# flow_sensor.net
KiCad netlist of a schematic drawn in EAGLE
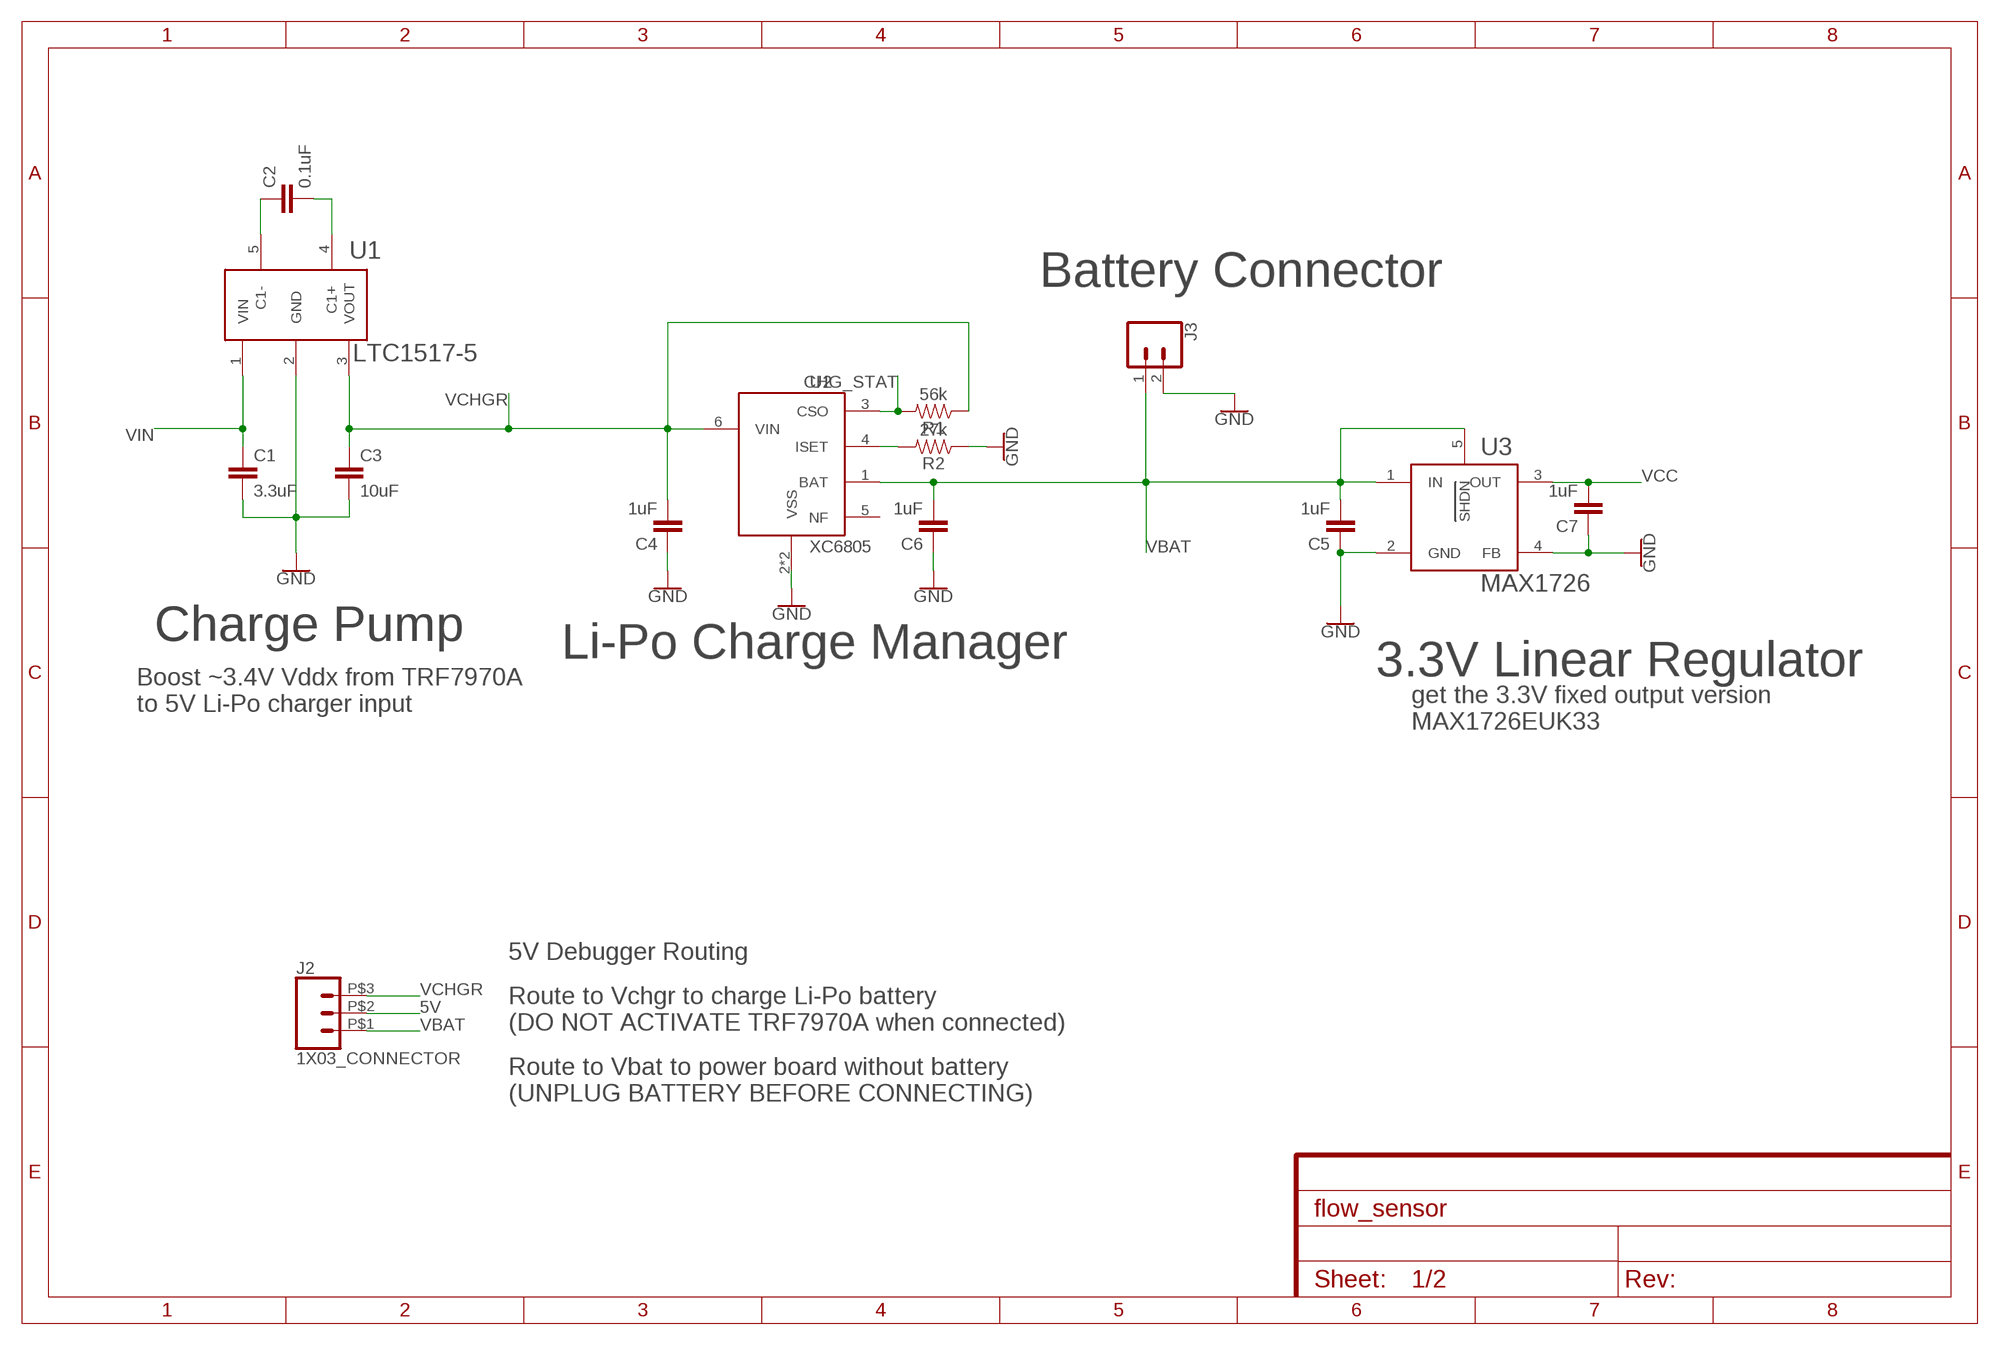
[diagram p0: schematic, sheet 1, part 1 of 2]
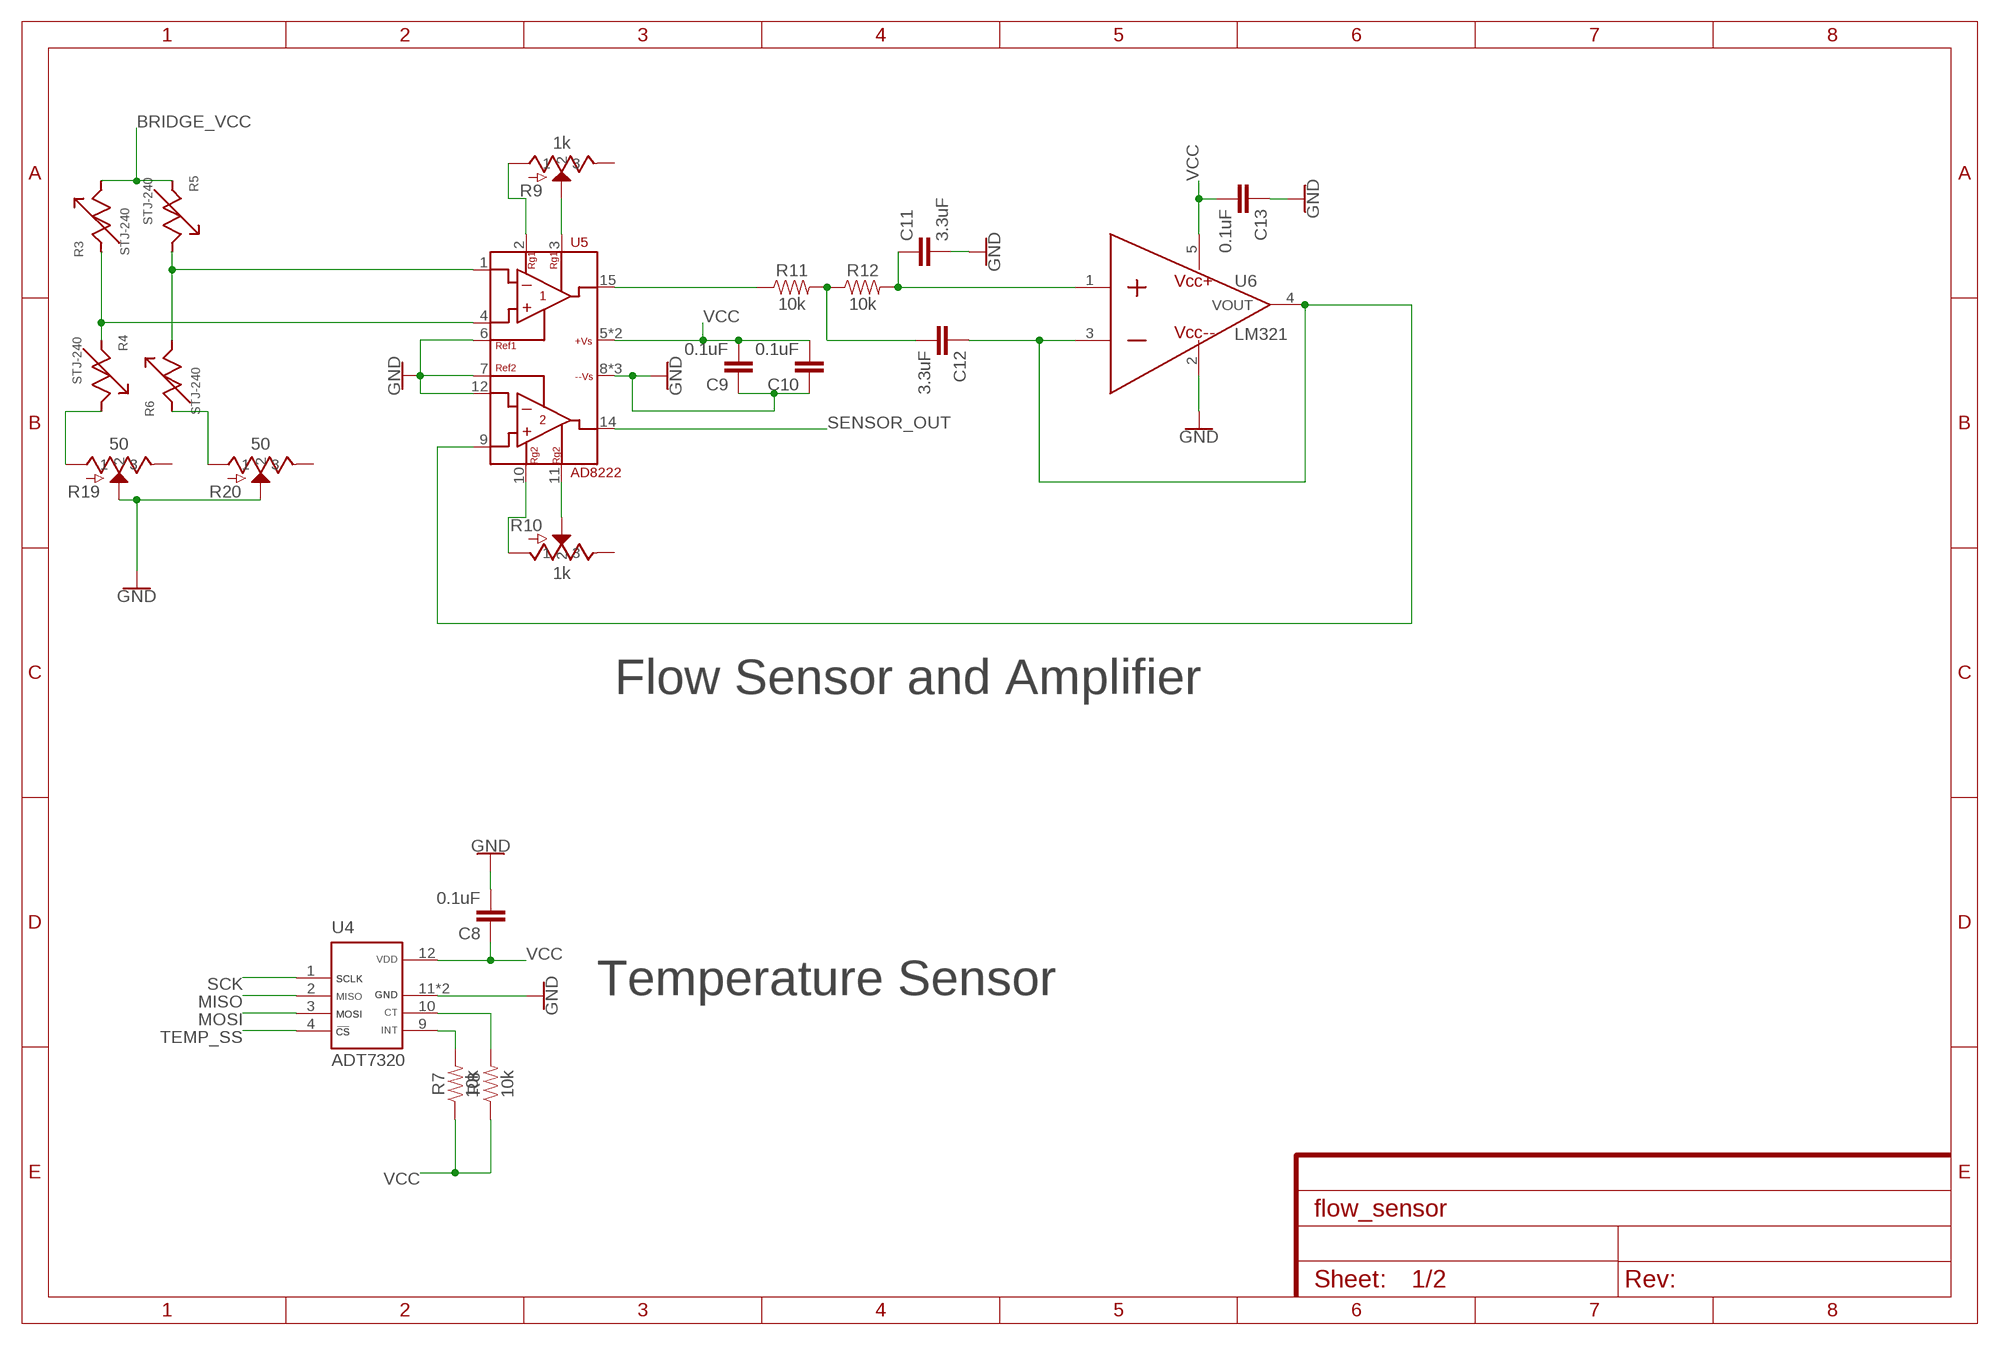
[diagram p1: schematic, sheet 1, part 2 of 2]
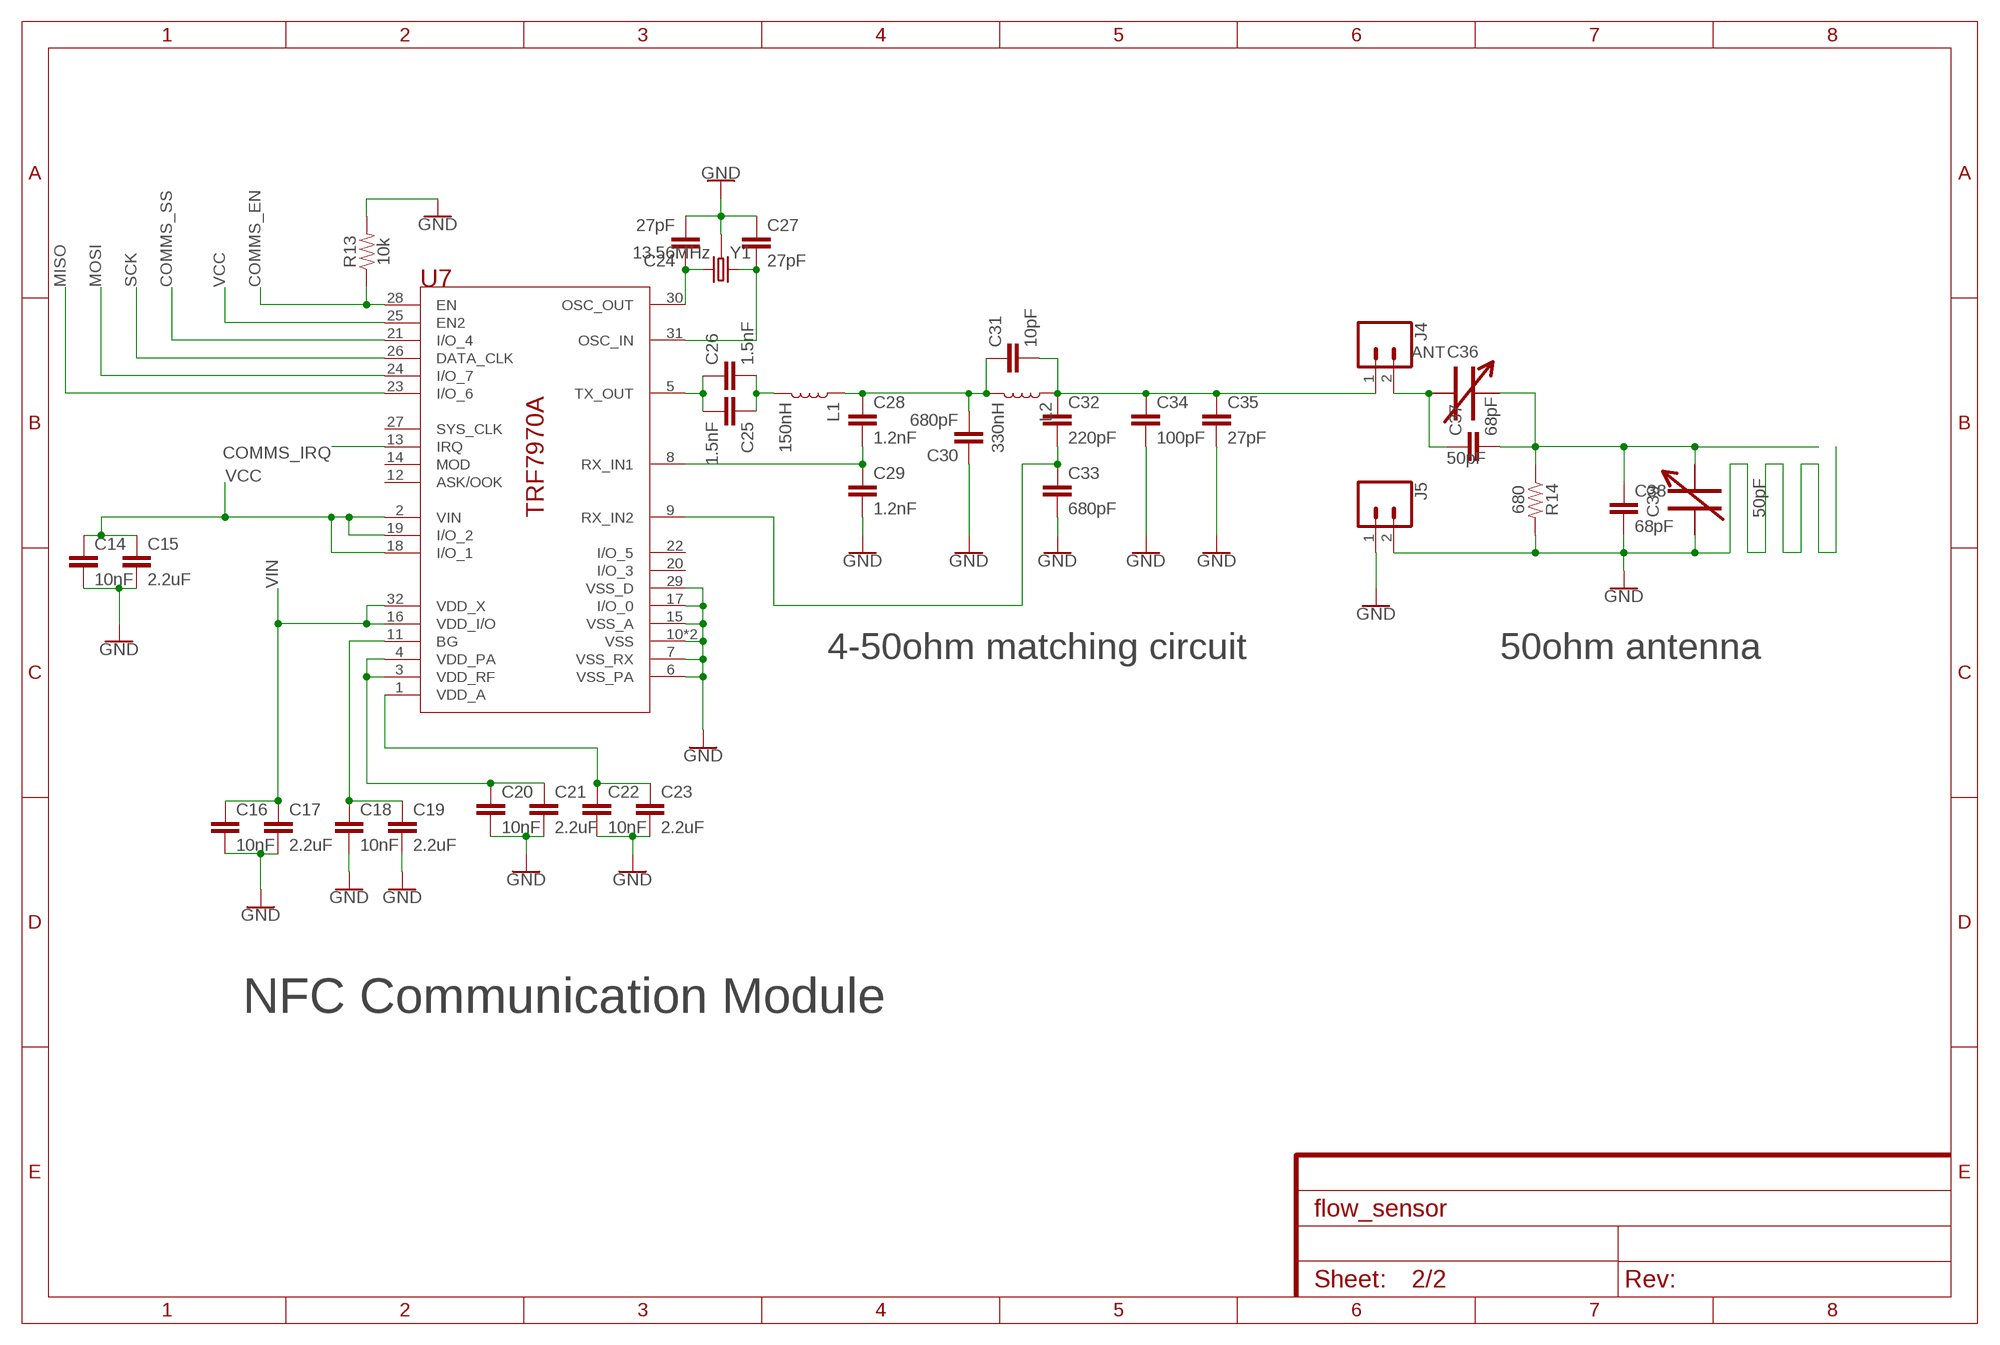
[diagram p2: schematic, sheet 2, part 1 of 2]
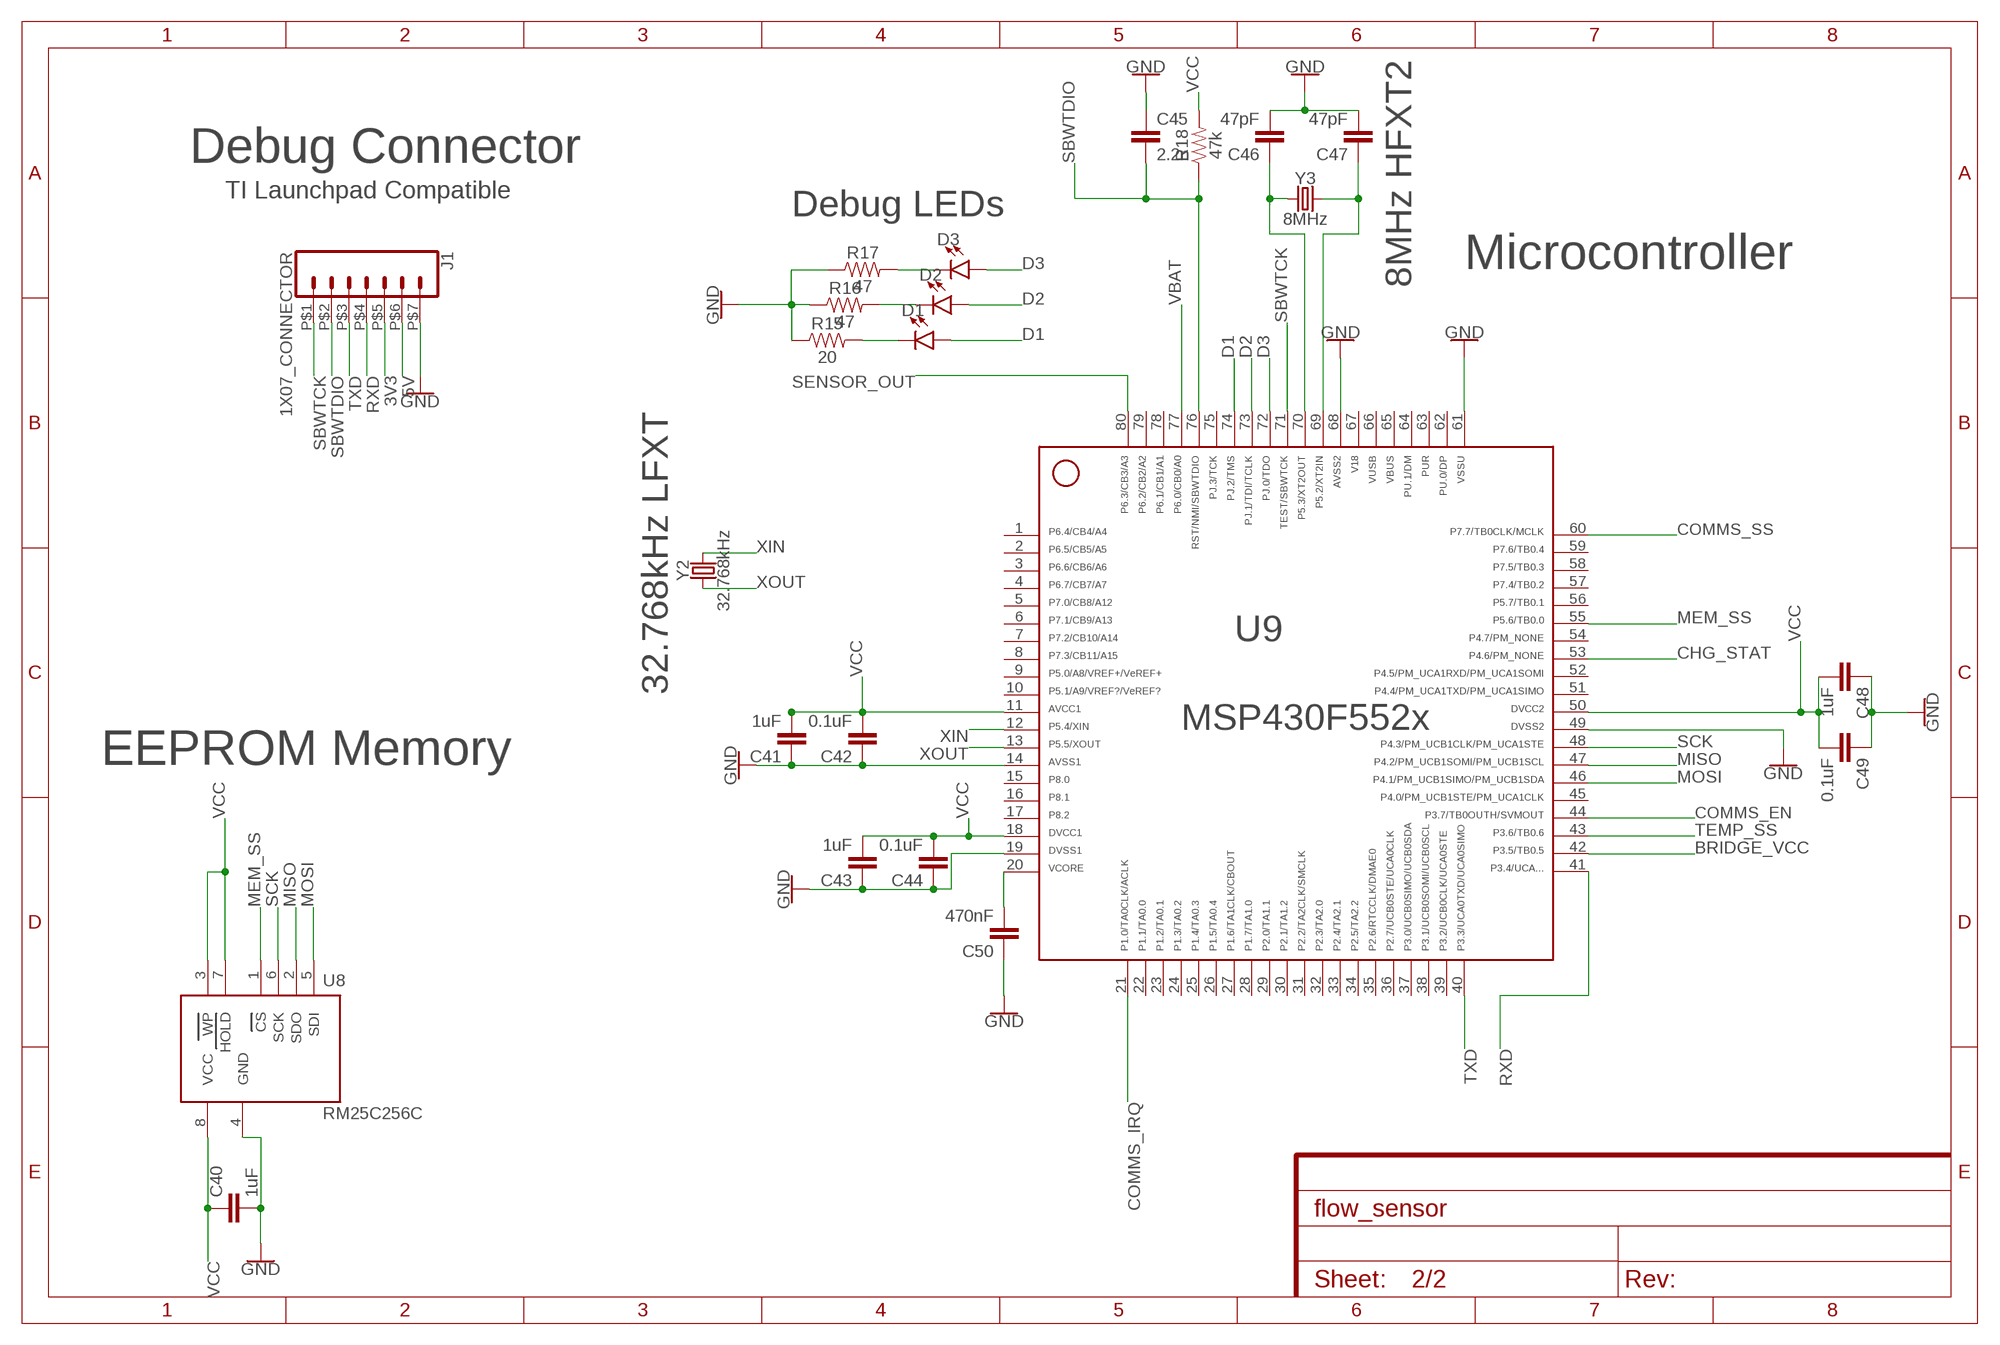
[diagram p3: schematic, sheet 2, part 2 of 2]

(export (version "E")
  (design (tool "Eeschema 10.0.6"))
  (components
    (comp (ref "C14")
      (value "10nF")
      (footprint "eagle-import:0603")
      (libsource (lib "eagle-import") (part "CAPACITOR_NONPOLARIZED"))
    )
    (comp (ref "C15")
      (value "2.2uF")
      (footprint "eagle-import:0603")
      (libsource (lib "eagle-import") (part "CAPACITOR_NONPOLARIZED"))
    )
    (comp (ref "C16")
      (value "10nF")
      (footprint "eagle-import:0603")
      (libsource (lib "eagle-import") (part "CAPACITOR_NONPOLARIZED"))
    )
    (comp (ref "C17")
      (value "2.2uF")
      (footprint "eagle-import:0603")
      (libsource (lib "eagle-import") (part "CAPACITOR_NONPOLARIZED"))
    )
    (comp (ref "C18")
      (value "10nF")
      (footprint "eagle-import:0603")
      (libsource (lib "eagle-import") (part "CAPACITOR_NONPOLARIZED"))
    )
    (comp (ref "C19")
      (value "2.2uF")
      (footprint "eagle-import:0603")
      (libsource (lib "eagle-import") (part "CAPACITOR_NONPOLARIZED"))
    )
    (comp (ref "C20")
      (value "10nF")
      (footprint "eagle-import:0603")
      (libsource (lib "eagle-import") (part "CAPACITOR_NONPOLARIZED"))
    )
    (comp (ref "C21")
      (value "2.2uF")
      (footprint "eagle-import:0603")
      (libsource (lib "eagle-import") (part "CAPACITOR_NONPOLARIZED"))
    )
    (comp (ref "C22")
      (value "10nF")
      (footprint "eagle-import:0603")
      (libsource (lib "eagle-import") (part "CAPACITOR_NONPOLARIZED"))
    )
    (comp (ref "C23")
      (value "2.2uF")
      (footprint "eagle-import:0603")
      (libsource (lib "eagle-import") (part "CAPACITOR_NONPOLARIZED"))
    )
    (comp (ref "C24")
      (value "27pF")
      (footprint "eagle-import:0603")
      (libsource (lib "eagle-import") (part "CAPACITOR_NONPOLARIZED"))
    )
    (comp (ref "C25")
      (value "1.5nF")
      (footprint "eagle-import:0603")
      (libsource (lib "eagle-import") (part "CAPACITOR_NONPOLARIZED"))
    )
    (comp (ref "C26")
      (value "1.5nF")
      (footprint "eagle-import:0603")
      (libsource (lib "eagle-import") (part "CAPACITOR_NONPOLARIZED"))
    )
    (comp (ref "C27")
      (value "27pF")
      (footprint "eagle-import:0603")
      (libsource (lib "eagle-import") (part "CAPACITOR_NONPOLARIZED"))
    )
    (comp (ref "C28")
      (value "1.2nF")
      (footprint "eagle-import:0603")
      (libsource (lib "eagle-import") (part "CAPACITOR_NONPOLARIZED"))
    )
    (comp (ref "C29")
      (value "1.2nF")
      (footprint "eagle-import:0603")
      (libsource (lib "eagle-import") (part "CAPACITOR_NONPOLARIZED"))
    )
    (comp (ref "C30")
      (value "680pF")
      (footprint "eagle-import:0603")
      (libsource (lib "eagle-import") (part "CAPACITOR_NONPOLARIZED"))
    )
    (comp (ref "C31")
      (value "10pF")
      (footprint "eagle-import:0603")
      (libsource (lib "eagle-import") (part "CAPACITOR_NONPOLARIZED"))
    )
    (comp (ref "C32")
      (value "220pF")
      (footprint "eagle-import:0603")
      (libsource (lib "eagle-import") (part "CAPACITOR_NONPOLARIZED"))
    )
    (comp (ref "C33")
      (value "680pF")
      (footprint "eagle-import:0603")
      (libsource (lib "eagle-import") (part "CAPACITOR_NONPOLARIZED"))
    )
    (comp (ref "C34")
      (value "100pF")
      (footprint "eagle-import:0603")
      (libsource (lib "eagle-import") (part "CAPACITOR_NONPOLARIZED"))
    )
    (comp (ref "C35")
      (value "27pF")
      (footprint "eagle-import:0603")
      (libsource (lib "eagle-import") (part "CAPACITOR_NONPOLARIZED"))
    )
    (comp (ref "C36")
      (value "50pF")
      (footprint "eagle-import:TZY2_TRIM_CAP")
      (libsource (lib "eagle-import") (part "TZY2_TRIM_CAP"))
    )
    (comp (ref "C37")
      (value "68pF")
      (footprint "eagle-import:C2.5-2")
      (libsource (lib "eagle-import") (part "C2.5/2"))
    )
    (comp (ref "C38")
      (value "68pF")
      (footprint "eagle-import:C2.5-2")
      (libsource (lib "eagle-import") (part "C2.5/2"))
    )
    (comp (ref "C39")
      (value "50pF")
      (footprint "eagle-import:TZY2_TRIM_CAP")
      (libsource (lib "eagle-import") (part "TZY2_TRIM_CAP"))
    )
    (comp (ref "C40")
      (value "1uF")
      (footprint "eagle-import:0603")
      (libsource (lib "eagle-import") (part "CAPACITOR_NONPOLARIZED"))
    )
    (comp (ref "C41")
      (value "1uF")
      (footprint "eagle-import:0603")
      (libsource (lib "eagle-import") (part "CAPACITOR_NONPOLARIZED"))
    )
    (comp (ref "C42")
      (value "0.1uF")
      (footprint "eagle-import:0603")
      (libsource (lib "eagle-import") (part "CAPACITOR_NONPOLARIZED"))
    )
    (comp (ref "C43")
      (value "1uF")
      (footprint "eagle-import:0603")
      (libsource (lib "eagle-import") (part "CAPACITOR_NONPOLARIZED"))
    )
    (comp (ref "C44")
      (value "0.1uF")
      (footprint "eagle-import:0603")
      (libsource (lib "eagle-import") (part "CAPACITOR_NONPOLARIZED"))
    )
    (comp (ref "C45")
      (value "2.2n")
      (footprint "eagle-import:0603")
      (libsource (lib "eagle-import") (part "CAPACITOR_NONPOLARIZED"))
    )
    (comp (ref "C46")
      (value "47pF")
      (footprint "eagle-import:0603")
      (libsource (lib "eagle-import") (part "CAPACITOR_NONPOLARIZED"))
    )
    (comp (ref "C47")
      (value "47pF")
      (footprint "eagle-import:0603")
      (libsource (lib "eagle-import") (part "CAPACITOR_NONPOLARIZED"))
    )
    (comp (ref "C48")
      (value "1uF")
      (footprint "eagle-import:0603")
      (libsource (lib "eagle-import") (part "CAPACITOR_NONPOLARIZED"))
    )
    (comp (ref "C49")
      (value "0.1uF")
      (footprint "eagle-import:0603")
      (libsource (lib "eagle-import") (part "CAPACITOR_NONPOLARIZED"))
    )
    (comp (ref "C50")
      (value "470nF")
      (footprint "eagle-import:0603")
      (libsource (lib "eagle-import") (part "CAPACITOR_NONPOLARIZED"))
    )
    (comp (ref "D1")
      (value "LED0603")
      (footprint "eagle-import:LED-0603")
      (libsource (lib "eagle-import") (part "LED0603"))
    )
    (comp (ref "D2")
      (value "LED0603")
      (footprint "eagle-import:LED-0603")
      (libsource (lib "eagle-import") (part "LED0603"))
    )
    (comp (ref "D3")
      (value "LED0603")
      (footprint "eagle-import:LED-0603")
      (libsource (lib "eagle-import") (part "LED0603"))
    )
    (comp (ref "J1")
      (value "1X07_CONNECTOR")
      (footprint "eagle-import:1X07_SMD_HEADER")
      (libsource (lib "eagle-import") (part "1X07_CONNECTOR"))
    )
    (comp (ref "J4")
      (value "CONN_02")
      (footprint "eagle-import:1X02")
      (libsource (lib "eagle-import") (part "CONN_02"))
    )
    (comp (ref "J5")
      (value "CONN_02")
      (footprint "eagle-import:1X02")
      (libsource (lib "eagle-import") (part "CONN_02"))
    )
    (comp (ref "L1")
      (value "150nH")
      (footprint "eagle-import:0603")
      (libsource (lib "eagle-import") (part "INDUCTOR"))
    )
    (comp (ref "L2")
      (value "330nH")
      (footprint "eagle-import:0603")
      (libsource (lib "eagle-import") (part "INDUCTOR"))
    )
    (comp (ref "R13")
      (value "10k")
      (footprint "eagle-import:0603")
      (libsource (lib "eagle-import") (part "RESISTOR"))
    )
    (comp (ref "R14")
      (value "680")
      (footprint "eagle-import:0603")
      (libsource (lib "eagle-import") (part "RESISTOR"))
    )
    (comp (ref "R15")
      (value "20")
      (footprint "eagle-import:0603")
      (libsource (lib "eagle-import") (part "RESISTOR"))
    )
    (comp (ref "R16")
      (value "47")
      (footprint "eagle-import:0603")
      (libsource (lib "eagle-import") (part "RESISTOR"))
    )
    (comp (ref "R17")
      (value "47")
      (footprint "eagle-import:0603")
      (libsource (lib "eagle-import") (part "RESISTOR"))
    )
    (comp (ref "R18")
      (value "47k")
      (footprint "eagle-import:0603")
      (libsource (lib "eagle-import") (part "RESISTOR"))
    )
    (comp (ref "U7")
      (value "TRF7970A")
      (footprint "eagle-import:QFN-32")
      (libsource (lib "eagle-import") (part "TRF7970A"))
    )
    (comp (ref "U8")
      (value "RM25C256C")
      (footprint "eagle-import:DFN8-2X3")
      (libsource (lib "eagle-import") (part "RM25C256C"))
    )
    (comp (ref "U9")
      (value "F552X---PN80")
      (footprint "eagle-import:PN80")
      (libsource (lib "eagle-import") (part "F552X---PN80"))
    )
    (comp (ref "Y1")
      (value "13.56MHz")
      (footprint "eagle-import:CRYSTAL-SMD-3.2X2.5MM")
      (libsource (lib "eagle-import") (part "CRYSTAL-GROUNDEDSMD-3.2X2.5"))
    )
    (comp (ref "Y2")
      (value "32.768kHz")
      (footprint "eagle-import:CRYSTAL-3.2X1.5")
      (libsource (lib "eagle-import") (part "CRYSTAL-3.2X1.5"))
    )
    (comp (ref "Y3")
      (value "8MHz")
      (footprint "eagle-import:CRYSTAL-3.2X2.5")
      (libsource (lib "eagle-import") (part "CRYSTAL-3.2X2.5"))
    )
    (comp (ref "C1")
      (value "3.3uF")
      (footprint "eagle-import:0603")
      (libsource (lib "eagle-import") (part "CAPACITOR_NONPOLARIZED"))
    )
    (comp (ref "C2")
      (value "0.1uF")
      (footprint "eagle-import:0603")
      (libsource (lib "eagle-import") (part "CAPACITOR_NONPOLARIZED"))
    )
    (comp (ref "C3")
      (value "10uF")
      (footprint "eagle-import:0603")
      (libsource (lib "eagle-import") (part "CAPACITOR_NONPOLARIZED"))
    )
    (comp (ref "C4")
      (value "1uF")
      (footprint "eagle-import:0603")
      (libsource (lib "eagle-import") (part "CAPACITOR_NONPOLARIZED"))
    )
    (comp (ref "C5")
      (value "1uF")
      (footprint "eagle-import:0603")
      (libsource (lib "eagle-import") (part "CAPACITOR_NONPOLARIZED"))
    )
    (comp (ref "C6")
      (value "1uF")
      (footprint "eagle-import:0603")
      (libsource (lib "eagle-import") (part "CAPACITOR_NONPOLARIZED"))
    )
    (comp (ref "C7")
      (value "1uF")
      (footprint "eagle-import:0603")
      (libsource (lib "eagle-import") (part "CAPACITOR_NONPOLARIZED"))
    )
    (comp (ref "C8")
      (value "0.1uF")
      (footprint "eagle-import:0603")
      (libsource (lib "eagle-import") (part "CAPACITOR_NONPOLARIZED"))
    )
    (comp (ref "C9")
      (value "0.1uF")
      (footprint "eagle-import:0603")
      (libsource (lib "eagle-import") (part "CAPACITOR_NONPOLARIZED"))
    )
    (comp (ref "C10")
      (value "0.1uF")
      (footprint "eagle-import:0603")
      (libsource (lib "eagle-import") (part "CAPACITOR_NONPOLARIZED"))
    )
    (comp (ref "C11")
      (value "3.3uF")
      (footprint "eagle-import:0603")
      (libsource (lib "eagle-import") (part "CAPACITOR_NONPOLARIZED"))
    )
    (comp (ref "C12")
      (value "3.3uF")
      (footprint "eagle-import:0603")
      (libsource (lib "eagle-import") (part "CAPACITOR_NONPOLARIZED"))
    )
    (comp (ref "C13")
      (value "0.1uF")
      (footprint "eagle-import:0603")
      (libsource (lib "eagle-import") (part "CAPACITOR_NONPOLARIZED"))
    )
    (comp (ref "J2")
      (value "1X03_CONNECTOR")
      (footprint "eagle-import:1X03_SMD_HEADER")
      (libsource (lib "eagle-import") (part "1X03_CONNECTOR"))
    )
    (comp (ref "J3")
      (value "CONN_021X02_NO_SILK")
      (footprint "eagle-import:1X02_NO_SILK")
      (libsource (lib "eagle-import") (part "CONN_021X02_NO_SILK"))
    )
    (comp (ref "R1")
      (value "56k")
      (footprint "eagle-import:0603")
      (libsource (lib "eagle-import") (part "RESISTOR"))
    )
    (comp (ref "R2")
      (value "27k")
      (footprint "eagle-import:0603")
      (libsource (lib "eagle-import") (part "RESISTOR"))
    )
    (comp (ref "R3")
      (value "STJ-240")
      (footprint "eagle-import:SOIC-8-NOCREAM")
      (libsource (lib "eagle-import") (part "STJ-240"))
    )
    (comp (ref "R4")
      (value "STJ-240")
      (footprint "eagle-import:SOIC-8-NOCREAM")
      (libsource (lib "eagle-import") (part "STJ-240"))
    )
    (comp (ref "R5")
      (value "STJ-240")
      (footprint "eagle-import:SOIC-8-NOCREAM")
      (libsource (lib "eagle-import") (part "STJ-240"))
    )
    (comp (ref "R6")
      (value "STJ-240")
      (footprint "eagle-import:SOIC-8-NOCREAM")
      (libsource (lib "eagle-import") (part "STJ-240"))
    )
    (comp (ref "R7")
      (value "10k")
      (footprint "eagle-import:0603")
      (libsource (lib "eagle-import") (part "RESISTOR"))
    )
    (comp (ref "R8")
      (value "10k")
      (footprint "eagle-import:0603")
      (libsource (lib "eagle-import") (part "RESISTOR"))
    )
    (comp (ref "R9")
      (value "1k")
      (footprint "eagle-import:ST-32ETA")
      (libsource (lib "eagle-import") (part "ST-32ETA"))
    )
    (comp (ref "R10")
      (value "1k")
      (footprint "eagle-import:ST-32ETA")
      (libsource (lib "eagle-import") (part "ST-32ETA"))
    )
    (comp (ref "R11")
      (value "10k")
      (footprint "eagle-import:0603")
      (libsource (lib "eagle-import") (part "RESISTOR"))
    )
    (comp (ref "R12")
      (value "10k")
      (footprint "eagle-import:0603")
      (libsource (lib "eagle-import") (part "RESISTOR"))
    )
    (comp (ref "R19")
      (value "50")
      (footprint "eagle-import:ST-32ETA")
      (libsource (lib "eagle-import") (part "ST-32ETA"))
    )
    (comp (ref "R20")
      (value "50")
      (footprint "eagle-import:ST-32ETA")
      (libsource (lib "eagle-import") (part "ST-32ETA"))
    )
    (comp (ref "U1")
      (value "LTC1517-5")
      (footprint "eagle-import:SOT-23-5")
      (libsource (lib "eagle-import") (part "LTC1517-5"))
    )
    (comp (ref "U2")
      (value "XC6805")
      (footprint "eagle-import:DFN6-1.8X2.0")
      (libsource (lib "eagle-import") (part "XC6805"))
    )
    (comp (ref "U3")
      (value "MAX1726")
      (footprint "eagle-import:SOT-23-5")
      (libsource (lib "eagle-import") (part "MAX1726"))
    )
    (comp (ref "U4")
      (value "ADT7320")
      (footprint "eagle-import:QFN16-4X4")
      (libsource (lib "eagle-import") (part "ADT7320"))
    )
    (comp (ref "U5")
      (value "AD8222")
      (footprint "eagle-import:QFN16-4X4")
      (libsource (lib "eagle-import") (part "AD8222"))
    )
    (comp (ref "U6")
      (value "LM321")
      (footprint "eagle-import:SOT-23-5")
      (libsource (lib "eagle-import") (part "LM321"))
    )
  )
  (nets
    (net (code "1") (name "3V3") (class "Default")
      (node (ref "J1") (pin "P$5") (pinfunction "5_P$5") (pintype "passive"))
    )
    (net (code "2") (name "5V") (class "Default")
      (node (ref "J1") (pin "P$6") (pinfunction "6_P$6") (pintype "passive"))
      (node (ref "J2") (pin "P$2") (pinfunction "2_P$2") (pintype "passive"))
    )
    (net (code "3") (name "65") (class "Default")
      (node (ref "U9") (pin "65") (pinfunction "65_65") (pintype "power_in"))
    )
    (net (code "4") (name "66") (class "Default")
      (node (ref "U9") (pin "66") (pinfunction "66_66") (pintype "power_in"))
    )
    (net (code "5") (name "67") (class "Default")
      (node (ref "U9") (pin "67") (pinfunction "67_67") (pintype "power_in"))
    )
    (net (code "6") (name "ANT") (class "Default")
      (node (ref "C31") (pin "2") (pinfunction "2_2") (pintype "passive"))
      (node (ref "C32") (pin "1") (pinfunction "1_1") (pintype "passive"))
      (node (ref "C34") (pin "1") (pinfunction "1_1") (pintype "passive"))
      (node (ref "C35") (pin "1") (pinfunction "1_1") (pintype "passive"))
      (node (ref "J4") (pin "1") (pinfunction "1_1") (pintype "passive"))
      (node (ref "L2") (pin "1") (pinfunction "1_1") (pintype "passive"))
    )
    (net (code "7") (name "BRIDGE_VCC") (class "Default")
      (node (ref "R3") (pin "8") (pinfunction "P$2_8") (pintype "bidirectional"))
      (node (ref "R5") (pin "1") (pinfunction "P$1_1") (pintype "bidirectional"))
      (node (ref "U9") (pin "42") (pinfunction "42_42") (pintype "bidirectional"))
    )
    (net (code "8") (name "CHG_STAT") (class "Default")
      (node (ref "R1") (pin "2") (pinfunction "2_2") (pintype "passive"))
      (node (ref "U2") (pin "3") (pinfunction "CSO_3") (pintype "bidirectional"))
      (node (ref "U9") (pin "53") (pinfunction "53_53") (pintype "bidirectional"))
    )
    (net (code "9") (name "COMMS_EN") (class "Default")
      (node (ref "R13") (pin "1") (pinfunction "1_1") (pintype "passive"))
      (node (ref "U7") (pin "28") (pinfunction "EN_28") (pintype "bidirectional"))
      (node (ref "U9") (pin "44") (pinfunction "44_44") (pintype "bidirectional"))
    )
    (net (code "10") (name "COMMS_IRQ") (class "Default")
      (node (ref "U7") (pin "13") (pinfunction "IRQ_13") (pintype "bidirectional"))
      (node (ref "U9") (pin "21") (pinfunction "21_21") (pintype "bidirectional"))
    )
    (net (code "11") (name "COMMS_SS") (class "Default")
      (node (ref "U7") (pin "21") (pinfunction "I/O_4_21") (pintype "bidirectional"))
      (node (ref "U9") (pin "60") (pinfunction "60_60") (pintype "bidirectional"))
    )
    (net (code "12") (name "D1") (class "Default")
      (node (ref "D1") (pin "A") (pinfunction "A_A") (pintype "passive"))
      (node (ref "U9") (pin "74") (pinfunction "74_74") (pintype "bidirectional"))
    )
    (net (code "13") (name "D2") (class "Default")
      (node (ref "D2") (pin "A") (pinfunction "A_A") (pintype "passive"))
      (node (ref "U9") (pin "73") (pinfunction "73_73") (pintype "bidirectional"))
    )
    (net (code "14") (name "D3") (class "Default")
      (node (ref "D3") (pin "A") (pinfunction "A_A") (pintype "passive"))
      (node (ref "U9") (pin "72") (pinfunction "72_72") (pintype "bidirectional"))
    )
    (net (code "15") (name "GND") (class "Default")
      (node (ref "C1") (pin "2") (pinfunction "2_2") (pintype "passive"))
      (node (ref "C10") (pin "1") (pinfunction "1_1") (pintype "passive"))
      (node (ref "C11") (pin "2") (pinfunction "2_2") (pintype "passive"))
      (node (ref "C13") (pin "1") (pinfunction "1_1") (pintype "passive"))
      (node (ref "C14") (pin "2") (pinfunction "2_2") (pintype "passive"))
      (node (ref "C15") (pin "2") (pinfunction "2_2") (pintype "passive"))
      (node (ref "C16") (pin "2") (pinfunction "2_2") (pintype "passive"))
      (node (ref "C17") (pin "2") (pinfunction "2_2") (pintype "passive"))
      (node (ref "C18") (pin "2") (pinfunction "2_2") (pintype "passive"))
      (node (ref "C19") (pin "2") (pinfunction "2_2") (pintype "passive"))
      (node (ref "C20") (pin "2") (pinfunction "2_2") (pintype "passive"))
      (node (ref "C21") (pin "2") (pinfunction "2_2") (pintype "passive"))
      (node (ref "C22") (pin "2") (pinfunction "2_2") (pintype "passive"))
      (node (ref "C23") (pin "2") (pinfunction "2_2") (pintype "passive"))
      (node (ref "C24") (pin "2") (pinfunction "2_2") (pintype "passive"))
      (node (ref "C27") (pin "1") (pinfunction "1_1") (pintype "passive"))
      (node (ref "C29") (pin "2") (pinfunction "2_2") (pintype "passive"))
      (node (ref "C3") (pin "2") (pinfunction "2_2") (pintype "passive"))
      (node (ref "C30") (pin "1") (pinfunction "1_1") (pintype "passive"))
      (node (ref "C33") (pin "2") (pinfunction "2_2") (pintype "passive"))
      (node (ref "C34") (pin "2") (pinfunction "2_2") (pintype "passive"))
      (node (ref "C35") (pin "2") (pinfunction "2_2") (pintype "passive"))
      (node (ref "C38") (pin "2") (pinfunction "2_2") (pintype "passive"))
      (node (ref "C39") (pin "P$1") (pinfunction "P$1_P$1") (pintype "bidirectional"))
      (node (ref "C4") (pin "1") (pinfunction "1_1") (pintype "passive"))
      (node (ref "C40") (pin "2") (pinfunction "2_2") (pintype "passive"))
      (node (ref "C41") (pin "1") (pinfunction "1_1") (pintype "passive"))
      (node (ref "C42") (pin "1") (pinfunction "1_1") (pintype "passive"))
      (node (ref "C43") (pin "1") (pinfunction "1_1") (pintype "passive"))
      (node (ref "C44") (pin "1") (pinfunction "1_1") (pintype "passive"))
      (node (ref "C45") (pin "1") (pinfunction "1_1") (pintype "passive"))
      (node (ref "C46") (pin "2") (pinfunction "2_2") (pintype "passive"))
      (node (ref "C47") (pin "2") (pinfunction "2_2") (pintype "passive"))
      (node (ref "C48") (pin "1") (pinfunction "1_1") (pintype "passive"))
      (node (ref "C49") (pin "1") (pinfunction "1_1") (pintype "passive"))
      (node (ref "C5") (pin "1") (pinfunction "1_1") (pintype "passive"))
      (node (ref "C50") (pin "1") (pinfunction "1_1") (pintype "passive"))
      (node (ref "C6") (pin "1") (pinfunction "1_1") (pintype "passive"))
      (node (ref "C7") (pin "1") (pinfunction "1_1") (pintype "passive"))
      (node (ref "C8") (pin "2") (pinfunction "2_2") (pintype "passive"))
      (node (ref "C9") (pin "1") (pinfunction "1_1") (pintype "passive"))
      (node (ref "J1") (pin "P$7") (pinfunction "7_P$7") (pintype "passive"))
      (node (ref "J3") (pin "2") (pinfunction "2_2") (pintype "passive"))
      (node (ref "J5") (pin "1") (pinfunction "1_1") (pintype "passive"))
      (node (ref "J5") (pin "2") (pinfunction "2_2") (pintype "passive"))
      (node (ref "R13") (pin "2") (pinfunction "2_2") (pintype "passive"))
      (node (ref "R14") (pin "2") (pinfunction "2_2") (pintype "passive"))
      (node (ref "R15") (pin "1") (pinfunction "1_1") (pintype "passive"))
      (node (ref "R16") (pin "1") (pinfunction "1_1") (pintype "passive"))
      (node (ref "R17") (pin "1") (pinfunction "1_1") (pintype "passive"))
      (node (ref "R19") (pin "2") (pinfunction "2_2") (pintype "passive"))
      (node (ref "R2") (pin "1") (pinfunction "1_1") (pintype "passive"))
      (node (ref "R20") (pin "2") (pinfunction "2_2") (pintype "passive"))
      (node (ref "U1") (pin "2") (pinfunction "GND_2") (pintype "bidirectional"))
      (node (ref "U2") (pin "2") (pinfunction "VSS_2") (pintype "bidirectional"))
      (node (ref "U2") (pin "PAD") (pinfunction "VSS_PAD") (pintype "bidirectional"))
      (node (ref "U3") (pin "2") (pinfunction "GND_2") (pintype "bidirectional"))
      (node (ref "U3") (pin "4") (pinfunction "FB_4") (pintype "bidirectional"))
      (node (ref "U4") (pin "11") (pinfunction "GND_11") (pintype "bidirectional"))
      (node (ref "U4") (pin "EXP") (pinfunction "GND_EXP") (pintype "bidirectional"))
      (node (ref "U5") (pin "12") (pinfunction "-IN2_12") (pintype "bidirectional"))
      (node (ref "U5") (pin "13") (pinfunction "-VS_13") (pintype "bidirectional"))
      (node (ref "U5") (pin "6") (pinfunction "REF1_6") (pintype "bidirectional"))
      (node (ref "U5") (pin "7") (pinfunction "REF2_7") (pintype "bidirectional"))
      (node (ref "U5") (pin "8") (pinfunction "-VS_8") (pintype "bidirectional"))
      (node (ref "U5") (pin "EXP") (pinfunction "-VS_EXP") (pintype "bidirectional"))
      (node (ref "U6") (pin "2") (pinfunction "VCC-_2") (pintype "power_in"))
      (node (ref "U7") (pin "10") (pinfunction "VSS_10") (pintype "bidirectional"))
      (node (ref "U7") (pin "15") (pinfunction "VSS_A_15") (pintype "bidirectional"))
      (node (ref "U7") (pin "17") (pinfunction "I/O_0_17") (pintype "bidirectional"))
      (node (ref "U7") (pin "29") (pinfunction "VSS_D_29") (pintype "bidirectional"))
      (node (ref "U7") (pin "6") (pinfunction "VSS_PA_6") (pintype "bidirectional"))
      (node (ref "U7") (pin "7") (pinfunction "VSS_RX_7") (pintype "bidirectional"))
      (node (ref "U7") (pin "EP") (pinfunction "VSS_EP") (pintype "bidirectional"))
      (node (ref "U8") (pin "4") (pinfunction "GND_4") (pintype "bidirectional"))
      (node (ref "U9") (pin "14") (pinfunction "14_14") (pintype "power_in"))
      (node (ref "U9") (pin "19") (pinfunction "19_19") (pintype "power_in"))
      (node (ref "U9") (pin "49") (pinfunction "49_49") (pintype "power_in"))
      (node (ref "U9") (pin "61") (pinfunction "61_61") (pintype "power_in"))
      (node (ref "U9") (pin "68") (pinfunction "68_68") (pintype "power_in"))
      (node (ref "Y1") (pin "2") (pinfunction "3_2") (pintype "passive"))
      (node (ref "Y1") (pin "4") (pinfunction "3_4") (pintype "passive"))
    )
    (net (code "16") (name "MEM_SS") (class "Default")
      (node (ref "U8") (pin "1") (pinfunction "CS_1") (pintype "bidirectional"))
      (node (ref "U9") (pin "55") (pinfunction "55_55") (pintype "bidirectional"))
    )
    (net (code "17") (name "MISO") (class "Default")
      (node (ref "U4") (pin "2") (pinfunction "MISO_2") (pintype "bidirectional"))
      (node (ref "U7") (pin "23") (pinfunction "I/O_6_23") (pintype "bidirectional"))
      (node (ref "U8") (pin "2") (pinfunction "SDO_2") (pintype "bidirectional"))
      (node (ref "U9") (pin "47") (pinfunction "47_47") (pintype "bidirectional"))
    )
    (net (code "18") (name "MOSI") (class "Default")
      (node (ref "U4") (pin "3") (pinfunction "MOSI_3") (pintype "bidirectional"))
      (node (ref "U7") (pin "24") (pinfunction "I/O_7_24") (pintype "bidirectional"))
      (node (ref "U8") (pin "5") (pinfunction "SDI_5") (pintype "bidirectional"))
      (node (ref "U9") (pin "46") (pinfunction "46_46") (pintype "bidirectional"))
    )
    (net (code "19") (name "Net-(C12-Pad2)") (class "Default")
      (node (ref "C12") (pin "2") (pinfunction "2_2") (pintype "passive"))
      (node (ref "R11") (pin "2") (pinfunction "2_2") (pintype "passive"))
      (node (ref "R12") (pin "1") (pinfunction "1_1") (pintype "passive"))
    )
    (net (code "20") (name "Net-(C25-Pad1)") (class "Default")
      (node (ref "C25") (pin "1") (pinfunction "1_1") (pintype "passive"))
      (node (ref "C26") (pin "2") (pinfunction "2_2") (pintype "passive"))
      (node (ref "L1") (pin "2") (pinfunction "2_2") (pintype "passive"))
    )
    (net (code "21") (name "Net-(C28-Pad1)") (class "Default")
      (node (ref "C28") (pin "1") (pinfunction "1_1") (pintype "passive"))
      (node (ref "C30") (pin "2") (pinfunction "2_2") (pintype "passive"))
      (node (ref "C31") (pin "1") (pinfunction "1_1") (pintype "passive"))
      (node (ref "L1") (pin "1") (pinfunction "1_1") (pintype "passive"))
      (node (ref "L2") (pin "2") (pinfunction "2_2") (pintype "passive"))
    )
    (net (code "22") (name "Net-(C36-PadP$1)") (class "Default")
      (node (ref "C36") (pin "P$1") (pinfunction "P$1_P$1") (pintype "bidirectional"))
      (node (ref "C37") (pin "1") (pinfunction "1_1") (pintype "passive"))
      (node (ref "J4") (pin "2") (pinfunction "2_2") (pintype "passive"))
    )
    (net (code "23") (name "Net-(C36-PadP$2)") (class "Default")
      (node (ref "C36") (pin "P$2") (pinfunction "P$2_P$2") (pintype "bidirectional"))
      (node (ref "C37") (pin "2") (pinfunction "2_2") (pintype "passive"))
      (node (ref "C38") (pin "1") (pinfunction "1_1") (pintype "passive"))
      (node (ref "C39") (pin "P$2") (pinfunction "P$2_P$2") (pintype "bidirectional"))
      (node (ref "R14") (pin "1") (pinfunction "1_1") (pintype "passive"))
    )
    (net (code "24") (name "Net-(C46-Pad1)") (class "Default")
      (node (ref "C46") (pin "1") (pinfunction "1_1") (pintype "passive"))
      (node (ref "U9") (pin "70") (pinfunction "70_70") (pintype "bidirectional"))
      (node (ref "Y3") (pin "1") (pinfunction "1_1") (pintype "passive"))
    )
    (net (code "25") (name "Net-(C47-Pad1)") (class "Default")
      (node (ref "C47") (pin "1") (pinfunction "1_1") (pintype "passive"))
      (node (ref "U9") (pin "69") (pinfunction "69_69") (pintype "bidirectional"))
      (node (ref "Y3") (pin "2") (pinfunction "2_2") (pintype "passive"))
    )
    (net (code "26") (name "Net-(C50-Pad2)") (class "Default")
      (node (ref "C50") (pin "2") (pinfunction "2_2") (pintype "passive"))
      (node (ref "U9") (pin "20") (pinfunction "20_20") (pintype "power_in"))
    )
    (net (code "27") (name "Net-(D1-PadC)") (class "Default")
      (node (ref "D1") (pin "C") (pinfunction "C_C") (pintype "passive"))
      (node (ref "R15") (pin "2") (pinfunction "2_2") (pintype "passive"))
    )
    (net (code "28") (name "Net-(D2-PadC)") (class "Default")
      (node (ref "D2") (pin "C") (pinfunction "C_C") (pintype "passive"))
      (node (ref "R16") (pin "2") (pinfunction "2_2") (pintype "passive"))
    )
    (net (code "29") (name "Net-(D3-PadC)") (class "Default")
      (node (ref "D3") (pin "C") (pinfunction "C_C") (pintype "passive"))
      (node (ref "R17") (pin "2") (pinfunction "2_2") (pintype "passive"))
    )
    (net (code "30") (name "Net-(R3-P$1)") (class "Default")
      (node (ref "R3") (pin "1") (pinfunction "P$1_1") (pintype "bidirectional"))
      (node (ref "R4") (pin "1") (pinfunction "P$1_1") (pintype "bidirectional"))
      (node (ref "U5") (pin "4") (pinfunction "+IN1_4") (pintype "bidirectional"))
    )
    (net (code "31") (name "Net-(R4-P$2)") (class "Default")
      (node (ref "R19") (pin "1") (pinfunction "1_1") (pintype "passive"))
      (node (ref "R4") (pin "8") (pinfunction "P$2_8") (pintype "bidirectional"))
    )
    (net (code "32") (name "Net-(R5-P$2)") (class "Default")
      (node (ref "R5") (pin "8") (pinfunction "P$2_8") (pintype "bidirectional"))
      (node (ref "R6") (pin "8") (pinfunction "P$2_8") (pintype "bidirectional"))
      (node (ref "U5") (pin "1") (pinfunction "-IN1_1") (pintype "bidirectional"))
    )
    (net (code "33") (name "Net-(R6-P$1)") (class "Default")
      (node (ref "R20") (pin "1") (pinfunction "1_1") (pintype "passive"))
      (node (ref "R6") (pin "1") (pinfunction "P$1_1") (pintype "bidirectional"))
    )
    (net (code "34") (name "Net-(U1-C1+)") (class "Default")
      (node (ref "C2") (pin "2") (pinfunction "2_2") (pintype "passive"))
      (node (ref "U1") (pin "4") (pinfunction "C1+_4") (pintype "bidirectional"))
    )
    (net (code "35") (name "Net-(U1-C1-)") (class "Default")
      (node (ref "C2") (pin "1") (pinfunction "1_1") (pintype "passive"))
      (node (ref "U1") (pin "5") (pinfunction "C1-_5") (pintype "bidirectional"))
    )
    (net (code "36") (name "Net-(U2-ISET)") (class "Default")
      (node (ref "R2") (pin "2") (pinfunction "2_2") (pintype "passive"))
      (node (ref "U2") (pin "4") (pinfunction "ISET_4") (pintype "bidirectional"))
    )
    (net (code "37") (name "Net-(U4-CT)") (class "Default")
      (node (ref "R8") (pin "2") (pinfunction "2_2") (pintype "passive"))
      (node (ref "U4") (pin "10") (pinfunction "CT_10") (pintype "bidirectional"))
    )
    (net (code "38") (name "Net-(U4-INT)") (class "Default")
      (node (ref "R7") (pin "2") (pinfunction "2_2") (pintype "passive"))
      (node (ref "U4") (pin "9") (pinfunction "INT_9") (pintype "bidirectional"))
    )
    (net (code "39") (name "Net-(U5-+IN2)") (class "Default")
      (node (ref "C12") (pin "1") (pinfunction "1_1") (pintype "passive"))
      (node (ref "U5") (pin "9") (pinfunction "+IN2_9") (pintype "bidirectional"))
      (node (ref "U6") (pin "3") (pinfunction "IN-_3") (pintype "bidirectional"))
      (node (ref "U6") (pin "4") (pinfunction "VOUT_4") (pintype "bidirectional"))
    )
    (net (code "40") (name "Net-(U5-OUT1)") (class "Default")
      (node (ref "R11") (pin "1") (pinfunction "1_1") (pintype "passive"))
      (node (ref "U5") (pin "15") (pinfunction "OUT1_15") (pintype "bidirectional"))
    )
    (net (code "41") (name "Net-(U5-RG1')") (class "Default")
      (node (ref "R9") (pin "2") (pinfunction "2_2") (pintype "passive"))
      (node (ref "U5") (pin "3") (pinfunction "RG1'_3") (pintype "bidirectional"))
    )
    (net (code "42") (name "Net-(U5-RG1)") (class "Default")
      (node (ref "R9") (pin "1") (pinfunction "1_1") (pintype "passive"))
      (node (ref "U5") (pin "2") (pinfunction "RG1_2") (pintype "bidirectional"))
    )
    (net (code "43") (name "Net-(U5-RG2')") (class "Default")
      (node (ref "R10") (pin "2") (pinfunction "2_2") (pintype "passive"))
      (node (ref "U5") (pin "11") (pinfunction "RG2'_11") (pintype "bidirectional"))
    )
    (net (code "44") (name "Net-(U5-RG2)") (class "Default")
      (node (ref "R10") (pin "1") (pinfunction "1_1") (pintype "passive"))
      (node (ref "U5") (pin "10") (pinfunction "RG2_10") (pintype "bidirectional"))
    )
    (net (code "45") (name "Net-(U6-IN+)") (class "Default")
      (node (ref "C11") (pin "1") (pinfunction "1_1") (pintype "passive"))
      (node (ref "R12") (pin "2") (pinfunction "2_2") (pintype "passive"))
      (node (ref "U6") (pin "1") (pinfunction "IN+_1") (pintype "bidirectional"))
    )
    (net (code "46") (name "Net-(U7-BG)") (class "Default")
      (node (ref "C18") (pin "1") (pinfunction "1_1") (pintype "passive"))
      (node (ref "C19") (pin "1") (pinfunction "1_1") (pintype "passive"))
      (node (ref "U7") (pin "11") (pinfunction "BG_11") (pintype "bidirectional"))
    )
    (net (code "47") (name "Net-(U7-OSC_IN)") (class "Default")
      (node (ref "C27") (pin "2") (pinfunction "2_2") (pintype "passive"))
      (node (ref "U7") (pin "31") (pinfunction "OSC_IN_31") (pintype "bidirectional"))
      (node (ref "Y1") (pin "1") (pinfunction "1_1") (pintype "passive"))
    )
    (net (code "48") (name "Net-(U7-OSC_OUT)") (class "Default")
      (node (ref "C24") (pin "1") (pinfunction "1_1") (pintype "passive"))
      (node (ref "U7") (pin "30") (pinfunction "OSC_OUT_30") (pintype "bidirectional"))
      (node (ref "Y1") (pin "3") (pinfunction "2_3") (pintype "passive"))
    )
    (net (code "49") (name "Net-(U7-RX_IN1)") (class "Default")
      (node (ref "C28") (pin "2") (pinfunction "2_2") (pintype "passive"))
      (node (ref "C29") (pin "1") (pinfunction "1_1") (pintype "passive"))
      (node (ref "U7") (pin "8") (pinfunction "RX_IN1_8") (pintype "bidirectional"))
    )
    (net (code "50") (name "Net-(U7-RX_IN2)") (class "Default")
      (node (ref "C32") (pin "2") (pinfunction "2_2") (pintype "passive"))
      (node (ref "C33") (pin "1") (pinfunction "1_1") (pintype "passive"))
      (node (ref "U7") (pin "9") (pinfunction "RX_IN2_9") (pintype "bidirectional"))
    )
    (net (code "51") (name "Net-(U7-TX_OUT)") (class "Default")
      (node (ref "C25") (pin "2") (pinfunction "2_2") (pintype "passive"))
      (node (ref "C26") (pin "1") (pinfunction "1_1") (pintype "passive"))
      (node (ref "U7") (pin "5") (pinfunction "TX_OUT_5") (pintype "bidirectional"))
    )
    (net (code "52") (name "Net-(U7-VDD_A)") (class "Default")
      (node (ref "C22") (pin "1") (pinfunction "1_1") (pintype "passive"))
      (node (ref "C23") (pin "1") (pinfunction "1_1") (pintype "passive"))
      (node (ref "U7") (pin "1") (pinfunction "VDD_A_1") (pintype "bidirectional"))
    )
    (net (code "53") (name "Net-(U7-VDD_PA)") (class "Default")
      (node (ref "C20") (pin "1") (pinfunction "1_1") (pintype "passive"))
      (node (ref "C21") (pin "1") (pinfunction "1_1") (pintype "passive"))
      (node (ref "U7") (pin "3") (pinfunction "VDD_RF_3") (pintype "bidirectional"))
      (node (ref "U7") (pin "4") (pinfunction "VDD_PA_4") (pintype "bidirectional"))
    )
    (net (code "54") (name "RXD") (class "Default")
      (node (ref "J1") (pin "P$4") (pinfunction "4_P$4") (pintype "passive"))
      (node (ref "U9") (pin "41") (pinfunction "41_41") (pintype "bidirectional"))
    )
    (net (code "55") (name "SBWTCK") (class "Default")
      (node (ref "J1") (pin "P$1") (pinfunction "1_P$1") (pintype "passive"))
      (node (ref "U9") (pin "71") (pinfunction "71_71") (pintype "input"))
    )
    (net (code "56") (name "SBWTDIO") (class "Default")
      (node (ref "C45") (pin "2") (pinfunction "2_2") (pintype "passive"))
      (node (ref "J1") (pin "P$2") (pinfunction "2_P$2") (pintype "passive"))
      (node (ref "R18") (pin "1") (pinfunction "1_1") (pintype "passive"))
      (node (ref "U9") (pin "76") (pinfunction "76_76") (pintype "bidirectional"))
    )
    (net (code "57") (name "SCK") (class "Default")
      (node (ref "U4") (pin "1") (pinfunction "SCLK_1") (pintype "bidirectional"))
      (node (ref "U7") (pin "26") (pinfunction "DATA_CLK_26") (pintype "bidirectional"))
      (node (ref "U8") (pin "6") (pinfunction "SCK_6") (pintype "bidirectional"))
      (node (ref "U9") (pin "48") (pinfunction "48_48") (pintype "bidirectional"))
    )
    (net (code "58") (name "SENSOR_OUT") (class "Default")
      (node (ref "U5") (pin "14") (pinfunction "OUT2_14") (pintype "bidirectional"))
      (node (ref "U9") (pin "80") (pinfunction "80_80") (pintype "bidirectional"))
    )
    (net (code "59") (name "TEMP_SS") (class "Default")
      (node (ref "U4") (pin "4") (pinfunction "CS_4") (pintype "bidirectional"))
      (node (ref "U9") (pin "43") (pinfunction "43_43") (pintype "bidirectional"))
    )
    (net (code "60") (name "TXD") (class "Default")
      (node (ref "J1") (pin "P$3") (pinfunction "3_P$3") (pintype "passive"))
      (node (ref "U9") (pin "40") (pinfunction "40_40") (pintype "bidirectional"))
    )
    (net (code "61") (name "VBAT") (class "Default")
      (node (ref "C5") (pin "2") (pinfunction "2_2") (pintype "passive"))
      (node (ref "C6") (pin "2") (pinfunction "2_2") (pintype "passive"))
      (node (ref "J2") (pin "P$1") (pinfunction "1_P$1") (pintype "passive"))
      (node (ref "J3") (pin "1") (pinfunction "1_1") (pintype "passive"))
      (node (ref "U2") (pin "1") (pinfunction "BAT_1") (pintype "bidirectional"))
      (node (ref "U3") (pin "1") (pinfunction "IN_1") (pintype "bidirectional"))
      (node (ref "U3") (pin "5") (pinfunction "SHDN_5") (pintype "bidirectional"))
      (node (ref "U9") (pin "77") (pinfunction "77_77") (pintype "bidirectional"))
    )
    (net (code "62") (name "VCC") (class "Default")
      (node (ref "C10") (pin "2") (pinfunction "2_2") (pintype "passive"))
      (node (ref "C13") (pin "2") (pinfunction "2_2") (pintype "passive"))
      (node (ref "C14") (pin "1") (pinfunction "1_1") (pintype "passive"))
      (node (ref "C15") (pin "1") (pinfunction "1_1") (pintype "passive"))
      (node (ref "C40") (pin "1") (pinfunction "1_1") (pintype "passive"))
      (node (ref "C41") (pin "2") (pinfunction "2_2") (pintype "passive"))
      (node (ref "C42") (pin "2") (pinfunction "2_2") (pintype "passive"))
      (node (ref "C43") (pin "2") (pinfunction "2_2") (pintype "passive"))
      (node (ref "C44") (pin "2") (pinfunction "2_2") (pintype "passive"))
      (node (ref "C48") (pin "2") (pinfunction "2_2") (pintype "passive"))
      (node (ref "C49") (pin "2") (pinfunction "2_2") (pintype "passive"))
      (node (ref "C7") (pin "2") (pinfunction "2_2") (pintype "passive"))
      (node (ref "C8") (pin "1") (pinfunction "1_1") (pintype "passive"))
      (node (ref "C9") (pin "2") (pinfunction "2_2") (pintype "passive"))
      (node (ref "R18") (pin "2") (pinfunction "2_2") (pintype "passive"))
      (node (ref "R7") (pin "1") (pinfunction "1_1") (pintype "passive"))
      (node (ref "R8") (pin "1") (pinfunction "1_1") (pintype "passive"))
      (node (ref "U3") (pin "3") (pinfunction "OUT_3") (pintype "bidirectional"))
      (node (ref "U4") (pin "12") (pinfunction "VDD_12") (pintype "bidirectional"))
      (node (ref "U5") (pin "16") (pinfunction "+VS_16") (pintype "bidirectional"))
      (node (ref "U5") (pin "5") (pinfunction "+VS_5") (pintype "bidirectional"))
      (node (ref "U6") (pin "5") (pinfunction "VCC+_5") (pintype "power_in"))
      (node (ref "U7") (pin "18") (pinfunction "I/O_1_18") (pintype "bidirectional"))
      (node (ref "U7") (pin "19") (pinfunction "I/O_2_19") (pintype "bidirectional"))
      (node (ref "U7") (pin "2") (pinfunction "VIN_2") (pintype "bidirectional"))
      (node (ref "U7") (pin "25") (pinfunction "EN2_25") (pintype "bidirectional"))
      (node (ref "U8") (pin "3") (pinfunction "WP_3") (pintype "bidirectional"))
      (node (ref "U8") (pin "7") (pinfunction "HOLD_7") (pintype "bidirectional"))
      (node (ref "U8") (pin "8") (pinfunction "VCC_8") (pintype "bidirectional"))
      (node (ref "U9") (pin "11") (pinfunction "11_11") (pintype "power_in"))
      (node (ref "U9") (pin "18") (pinfunction "18_18") (pintype "power_in"))
      (node (ref "U9") (pin "50") (pinfunction "50_50") (pintype "power_in"))
    )
    (net (code "63") (name "VCHGR") (class "Default")
      (node (ref "C3") (pin "1") (pinfunction "1_1") (pintype "passive"))
      (node (ref "C4") (pin "2") (pinfunction "2_2") (pintype "passive"))
      (node (ref "J2") (pin "P$3") (pinfunction "3_P$3") (pintype "passive"))
      (node (ref "R1") (pin "1") (pinfunction "1_1") (pintype "passive"))
      (node (ref "U1") (pin "3") (pinfunction "VOUT_3") (pintype "bidirectional"))
      (node (ref "U2") (pin "6") (pinfunction "VIN_6") (pintype "bidirectional"))
    )
    (net (code "64") (name "VIN") (class "Default")
      (node (ref "C1") (pin "1") (pinfunction "1_1") (pintype "passive"))
      (node (ref "C16") (pin "1") (pinfunction "1_1") (pintype "passive"))
      (node (ref "C17") (pin "1") (pinfunction "1_1") (pintype "passive"))
      (node (ref "U1") (pin "1") (pinfunction "VIN_1") (pintype "bidirectional"))
      (node (ref "U7") (pin "16") (pinfunction "VDD_I/O_16") (pintype "bidirectional"))
      (node (ref "U7") (pin "32") (pinfunction "VDD_X_32") (pintype "bidirectional"))
    )
    (net (code "65") (name "XIN") (class "Default")
      (node (ref "U9") (pin "12") (pinfunction "12_12") (pintype "bidirectional"))
      (node (ref "Y2") (pin "P$2") (pinfunction "2_P$2") (pintype "passive"))
    )
    (net (code "66") (name "XOUT") (class "Default")
      (node (ref "U9") (pin "13") (pinfunction "13_13") (pintype "bidirectional"))
      (node (ref "Y2") (pin "P$1") (pinfunction "1_P$1") (pintype "passive"))
    )
    (net (code "67") (name "unconnected-(R9-Pad3)") (class "Default")
      (node (ref "R9") (pin "3") (pinfunction "3_3") (pintype "passive"))
    )
    (net (code "68") (name "unconnected-(R10-Pad3)") (class "Default")
      (node (ref "R10") (pin "3") (pinfunction "3_3") (pintype "passive"))
    )
    (net (code "69") (name "unconnected-(R19-Pad3)") (class "Default")
      (node (ref "R19") (pin "3") (pinfunction "3_3") (pintype "passive"))
    )
    (net (code "70") (name "unconnected-(R20-Pad3)") (class "Default")
      (node (ref "R20") (pin "3") (pinfunction "3_3") (pintype "passive"))
    )
    (net (code "71") (name "unconnected-(U2-NF-Pad5)") (class "Default")
      (node (ref "U2") (pin "5") (pinfunction "NF_5") (pintype "bidirectional"))
    )
    (net (code "72") (name "unconnected-(U7-ASK{slash}OOK-Pad12)") (class "Default")
      (node (ref "U7") (pin "12") (pinfunction "ASK/OOK_12") (pintype "bidirectional"))
    )
    (net (code "73") (name "unconnected-(U7-I{slash}O_3-Pad20)") (class "Default")
      (node (ref "U7") (pin "20") (pinfunction "I/O_3_20") (pintype "bidirectional"))
    )
    (net (code "74") (name "unconnected-(U7-I{slash}O_5-Pad22)") (class "Default")
      (node (ref "U7") (pin "22") (pinfunction "I/O_5_22") (pintype "bidirectional"))
    )
    (net (code "75") (name "unconnected-(U7-MOD-Pad14)") (class "Default")
      (node (ref "U7") (pin "14") (pinfunction "MOD_14") (pintype "bidirectional"))
    )
    (net (code "76") (name "unconnected-(U7-SYS_CLK-Pad27)") (class "Default")
      (node (ref "U7") (pin "27") (pinfunction "SYS_CLK_27") (pintype "bidirectional"))
    )
    (net (code "77") (name "unconnected-(U9-Pad1)") (class "Default")
      (node (ref "U9") (pin "1") (pinfunction "1_1") (pintype "bidirectional"))
    )
    (net (code "78") (name "unconnected-(U9-Pad2)") (class "Default")
      (node (ref "U9") (pin "2") (pinfunction "2_2") (pintype "bidirectional"))
    )
    (net (code "79") (name "unconnected-(U9-Pad3)") (class "Default")
      (node (ref "U9") (pin "3") (pinfunction "3_3") (pintype "bidirectional"))
    )
    (net (code "80") (name "unconnected-(U9-Pad4)") (class "Default")
      (node (ref "U9") (pin "4") (pinfunction "4_4") (pintype "bidirectional"))
    )
    (net (code "81") (name "unconnected-(U9-Pad5)") (class "Default")
      (node (ref "U9") (pin "5") (pinfunction "5_5") (pintype "bidirectional"))
    )
    (net (code "82") (name "unconnected-(U9-Pad6)") (class "Default")
      (node (ref "U9") (pin "6") (pinfunction "6_6") (pintype "bidirectional"))
    )
    (net (code "83") (name "unconnected-(U9-Pad7)") (class "Default")
      (node (ref "U9") (pin "7") (pinfunction "7_7") (pintype "bidirectional"))
    )
    (net (code "84") (name "unconnected-(U9-Pad8)") (class "Default")
      (node (ref "U9") (pin "8") (pinfunction "8_8") (pintype "bidirectional"))
    )
    (net (code "85") (name "unconnected-(U9-Pad9)") (class "Default")
      (node (ref "U9") (pin "9") (pinfunction "9_9") (pintype "bidirectional"))
    )
    (net (code "86") (name "unconnected-(U9-Pad10)") (class "Default")
      (node (ref "U9") (pin "10") (pinfunction "10_10") (pintype "bidirectional"))
    )
    (net (code "87") (name "unconnected-(U9-Pad15)") (class "Default")
      (node (ref "U9") (pin "15") (pinfunction "15_15") (pintype "bidirectional"))
    )
    (net (code "88") (name "unconnected-(U9-Pad16)") (class "Default")
      (node (ref "U9") (pin "16") (pinfunction "16_16") (pintype "bidirectional"))
    )
    (net (code "89") (name "unconnected-(U9-Pad17)") (class "Default")
      (node (ref "U9") (pin "17") (pinfunction "17_17") (pintype "bidirectional"))
    )
    (net (code "90") (name "unconnected-(U9-Pad22)") (class "Default")
      (node (ref "U9") (pin "22") (pinfunction "22_22") (pintype "bidirectional"))
    )
    (net (code "91") (name "unconnected-(U9-Pad23)") (class "Default")
      (node (ref "U9") (pin "23") (pinfunction "23_23") (pintype "bidirectional"))
    )
    (net (code "92") (name "unconnected-(U9-Pad24)") (class "Default")
      (node (ref "U9") (pin "24") (pinfunction "24_24") (pintype "bidirectional"))
    )
    (net (code "93") (name "unconnected-(U9-Pad25)") (class "Default")
      (node (ref "U9") (pin "25") (pinfunction "25_25") (pintype "bidirectional"))
    )
    (net (code "94") (name "unconnected-(U9-Pad26)") (class "Default")
      (node (ref "U9") (pin "26") (pinfunction "26_26") (pintype "bidirectional"))
    )
    (net (code "95") (name "unconnected-(U9-Pad27)") (class "Default")
      (node (ref "U9") (pin "27") (pinfunction "27_27") (pintype "bidirectional"))
    )
    (net (code "96") (name "unconnected-(U9-Pad28)") (class "Default")
      (node (ref "U9") (pin "28") (pinfunction "28_28") (pintype "bidirectional"))
    )
    (net (code "97") (name "unconnected-(U9-Pad29)") (class "Default")
      (node (ref "U9") (pin "29") (pinfunction "29_29") (pintype "bidirectional"))
    )
    (net (code "98") (name "unconnected-(U9-Pad30)") (class "Default")
      (node (ref "U9") (pin "30") (pinfunction "30_30") (pintype "bidirectional"))
    )
    (net (code "99") (name "unconnected-(U9-Pad31)") (class "Default")
      (node (ref "U9") (pin "31") (pinfunction "31_31") (pintype "bidirectional"))
    )
    (net (code "100") (name "unconnected-(U9-Pad32)") (class "Default")
      (node (ref "U9") (pin "32") (pinfunction "32_32") (pintype "bidirectional"))
    )
    (net (code "101") (name "unconnected-(U9-Pad33)") (class "Default")
      (node (ref "U9") (pin "33") (pinfunction "33_33") (pintype "bidirectional"))
    )
    (net (code "102") (name "unconnected-(U9-Pad34)") (class "Default")
      (node (ref "U9") (pin "34") (pinfunction "34_34") (pintype "bidirectional"))
    )
    (net (code "103") (name "unconnected-(U9-Pad35)") (class "Default")
      (node (ref "U9") (pin "35") (pinfunction "35_35") (pintype "bidirectional"))
    )
    (net (code "104") (name "unconnected-(U9-Pad36)") (class "Default")
      (node (ref "U9") (pin "36") (pinfunction "36_36") (pintype "bidirectional"))
    )
    (net (code "105") (name "unconnected-(U9-Pad37)") (class "Default")
      (node (ref "U9") (pin "37") (pinfunction "37_37") (pintype "bidirectional"))
    )
    (net (code "106") (name "unconnected-(U9-Pad38)") (class "Default")
      (node (ref "U9") (pin "38") (pinfunction "38_38") (pintype "bidirectional"))
    )
    (net (code "107") (name "unconnected-(U9-Pad39)") (class "Default")
      (node (ref "U9") (pin "39") (pinfunction "39_39") (pintype "bidirectional"))
    )
    (net (code "108") (name "unconnected-(U9-Pad45)") (class "Default")
      (node (ref "U9") (pin "45") (pinfunction "45_45") (pintype "bidirectional"))
    )
    (net (code "109") (name "unconnected-(U9-Pad51)") (class "Default")
      (node (ref "U9") (pin "51") (pinfunction "51_51") (pintype "bidirectional"))
    )
    (net (code "110") (name "unconnected-(U9-Pad52)") (class "Default")
      (node (ref "U9") (pin "52") (pinfunction "52_52") (pintype "bidirectional"))
    )
    (net (code "111") (name "unconnected-(U9-Pad54)") (class "Default")
      (node (ref "U9") (pin "54") (pinfunction "54_54") (pintype "bidirectional"))
    )
    (net (code "112") (name "unconnected-(U9-Pad56)") (class "Default")
      (node (ref "U9") (pin "56") (pinfunction "56_56") (pintype "bidirectional"))
    )
    (net (code "113") (name "unconnected-(U9-Pad57)") (class "Default")
      (node (ref "U9") (pin "57") (pinfunction "57_57") (pintype "bidirectional"))
    )
    (net (code "114") (name "unconnected-(U9-Pad58)") (class "Default")
      (node (ref "U9") (pin "58") (pinfunction "58_58") (pintype "bidirectional"))
    )
    (net (code "115") (name "unconnected-(U9-Pad59)") (class "Default")
      (node (ref "U9") (pin "59") (pinfunction "59_59") (pintype "bidirectional"))
    )
    (net (code "116") (name "unconnected-(U9-Pad62)") (class "Default")
      (node (ref "U9") (pin "62") (pinfunction "62_62") (pintype "bidirectional"))
    )
    (net (code "117") (name "unconnected-(U9-Pad63)") (class "Default")
      (node (ref "U9") (pin "63") (pinfunction "63_63") (pintype "bidirectional"))
    )
    (net (code "118") (name "unconnected-(U9-Pad64)") (class "Default")
      (node (ref "U9") (pin "64") (pinfunction "64_64") (pintype "bidirectional"))
    )
    (net (code "119") (name "unconnected-(U9-Pad75)") (class "Default")
      (node (ref "U9") (pin "75") (pinfunction "75_75") (pintype "bidirectional"))
    )
    (net (code "120") (name "unconnected-(U9-Pad78)") (class "Default")
      (node (ref "U9") (pin "78") (pinfunction "78_78") (pintype "bidirectional"))
    )
    (net (code "121") (name "unconnected-(U9-Pad79)") (class "Default")
      (node (ref "U9") (pin "79") (pinfunction "79_79") (pintype "bidirectional"))
    )
  )
)
